# Relay.net
KiCad netlist of a schematic drawn in Altium Designer
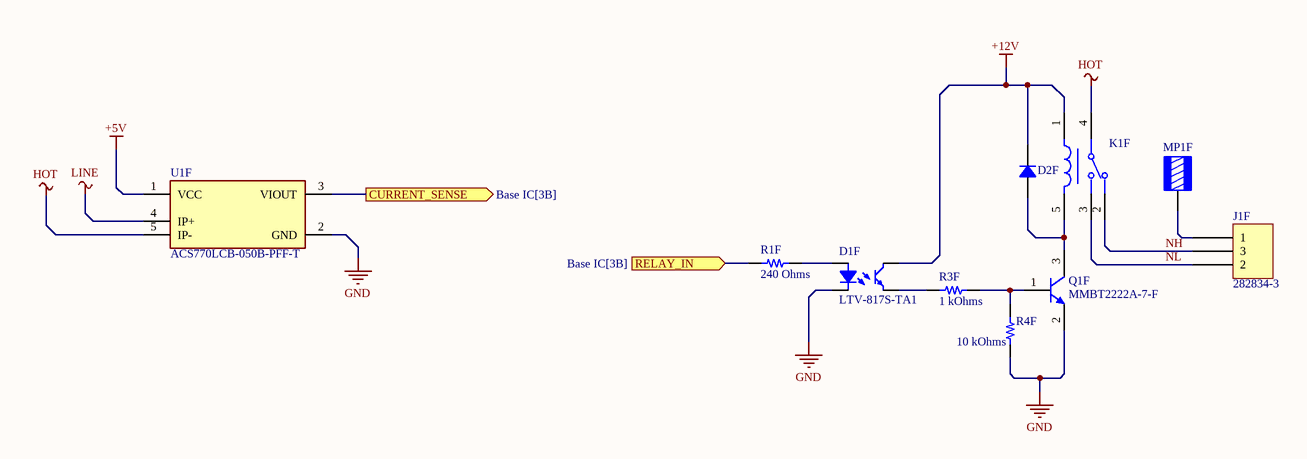
[diagram p0: Relay.SchDoc]

(export (version "E")
  (design (tool "Eeschema 10.0.6"))
  (components
    (comp (ref "D1F")
      (value "LTV-817S-TA1")
      (footprint "LITEON LTV-817")
      (description "OPTOISOLATR 5KV TRANSISTOR 4-SMD")
      (fields (field (name "MANUFACTURER") "Lite-On Inc."))
      (libsource (lib "Postgres Altium Library - altium_library") (part "Optoisolator"))
    )
    (comp (ref "D2F")
      (value "S2A-13-F")
      (footprint "DO214AA SMB")
      (description "DIODE GEN PURP 50V 1.5A SMB")
      (fields (field (name "MANUFACTURER") "Diodes Incorporated"))
      (libsource (lib "Postgres Altium Library - altium_library") (part "Diode"))
    )
    (comp (ref "J1F")
      (value "282834-3")
      (footprint "TE 282834-3")
      (description "TERM BLK 3P SIDE ENT 2.54MM PCB")
      (fields (field (name "VOLTAGE") "150V") (field (name "MANUFACTURER") "TE Connectivity AMP Connectors"))
      (libsource (lib "Postgres Altium Library - altium_library") (part "3 Pin"))
    )
    (comp (ref "K1F")
      (value "G2R-1-DC12")
      (footprint "FP-G2R-1-DC12-MFG")
      (description "RELAY GEN PURPOSE SPDT 10A 12V")
      (libsource (lib "Altium Content Vault") (part "ca5ce4f776bd4b8c9fc220deb446b63"))
    )
    (comp (ref "MP1F")
      (value "74650173R")
      (footprint "WURTH 74650173")
      (description "TERM REDCUBE M3 4PIN PCB")
      (fields (field (name "MANUFACTURER") "Würth Elektronik"))
      (libsource (lib "Postgres Altium Library - altium_library") (part "MOUNTING POINT"))
    )
    (comp (ref "Q1F")
      (value "MMBT2222A-7-F")
      (footprint "DIODES SOT-23-3")
      (description "TRANS NPN 40V 0.6A SOT23-3")
      (fields (field (name "MANUFACTURER") "Diodes Incorporated"))
      (libsource (lib "Postgres Altium Library - altium_library") (part "DIODES INC NPN SOT-23-3"))
    )
    (comp (ref "R1F")
      (value "240 Ohms")
      (footprint "RES 0603_1608")
      (description "RES 240 OHM 5% 1/8W 0603")
      (fields (field (name "PART NUMBER") "RK73B1JTTD241J") (field (name "TOLERANCE") "±5%"))
      (libsource (lib "Postgres Altium Library - altium_library") (part "Resistor"))
    )
    (comp (ref "R3F")
      (value "1 kOhms")
      (footprint "RES 0603_1608")
      (description "RES SMD 1K OHM 0.5% 1/10W 0603")
      (fields (field (name "PART NUMBER") "AT0603DRD071KL") (field (name "TOLERANCE") "±0.5%"))
      (libsource (lib "Postgres Altium Library - altium_library") (part "Resistor"))
    )
    (comp (ref "R4F")
      (value "10 kOhms")
      (footprint "RES 0603_1608")
      (description "RES SMD 10K OHM 0.1% 1/16W 0603")
      (fields (field (name "PART NUMBER") "CPF0603B10KE") (field (name "TOLERANCE") "±0.1%"))
      (libsource (lib "Postgres Altium Library - altium_library") (part "Resistor"))
    )
    (comp (ref "U1F")
      (value "ACS770LCB-050B-PFF-T")
      (footprint "FP-CB-5-PFF-MFG")
      (description "SENSOR CURRENT HALL 50A AC/DC")
      (libsource (lib "Altium Content Vault") (part "14cf2d2c5e445e47a38643444011565"))
    )
  )
  (nets
    (net (code "1") (name "+5V") (class "Default")
      (node (ref "U1F") (pin "1") (pinfunction "VCC_1") (pintype "power_in"))
    )
    (net (code "2") (name "+12V") (class "Default")
      (node (ref "D1F") (pin "4") (pinfunction "4_4") (pintype "passive"))
      (node (ref "D2F") (pin "2") (pinfunction "2_2") (pintype "passive"))
      (node (ref "K1F") (pin "1") (pinfunction "1_1") (pintype "passive"))
    )
    (net (code "3") (name "/CURRENT_SENSE") (class "Default")
      (node (ref "U1F") (pin "3") (pinfunction "VIOUT_3") (pintype "passive"))
    )
    (net (code "4") (name "/NH") (class "Default")
      (node (ref "J1F") (pin "3") (pinfunction "3_3") (pintype "passive"))
      (node (ref "K1F") (pin "2") (pinfunction "2_2") (pintype "passive"))
    )
    (net (code "5") (name "/NL") (class "Default")
      (node (ref "J1F") (pin "2") (pinfunction "2_2") (pintype "passive"))
      (node (ref "K1F") (pin "3") (pinfunction "3_3") (pintype "passive"))
    )
    (net (code "6") (name "/RELAY_IN") (class "Default")
      (node (ref "R1F") (pin "1") (pinfunction "1_1") (pintype "passive"))
    )
    (net (code "7") (name "GND") (class "Default")
      (node (ref "D1F") (pin "2") (pinfunction "2_2") (pintype "passive"))
      (node (ref "Q1F") (pin "2") (pinfunction "E_2") (pintype "passive"))
      (node (ref "R4F") (pin "1") (pinfunction "1_1") (pintype "passive"))
      (node (ref "U1F") (pin "2") (pinfunction "GND_2") (pintype "power_in"))
    )
    (net (code "8") (name "HOT") (class "Default")
      (node (ref "K1F") (pin "4") (pinfunction "4_4") (pintype "passive"))
      (node (ref "U1F") (pin "5") (pinfunction "IP-_5") (pintype "passive"))
    )
    (net (code "9") (name "LINE") (class "Default")
      (node (ref "U1F") (pin "4") (pinfunction "IP+_4") (pintype "passive"))
    )
    (net (code "10") (name "Net-(D1F-Pad1)") (class "Default")
      (node (ref "D1F") (pin "1") (pinfunction "1_1") (pintype "passive"))
      (node (ref "R1F") (pin "2") (pinfunction "2_2") (pintype "passive"))
    )
    (net (code "11") (name "Net-(D1F-Pad3)") (class "Default")
      (node (ref "D1F") (pin "3") (pinfunction "3_3") (pintype "passive"))
      (node (ref "R3F") (pin "1") (pinfunction "1_1") (pintype "passive"))
    )
    (net (code "12") (name "Net-(J1F-Pad1)") (class "Default")
      (node (ref "J1F") (pin "1") (pinfunction "1_1") (pintype "passive"))
      (node (ref "MP1F") (pin "1") (pinfunction "1_1") (pintype "passive"))
    )
    (net (code "13") (name "Net-(Q1F-B)") (class "Default")
      (node (ref "Q1F") (pin "1") (pinfunction "B_1") (pintype "passive"))
      (node (ref "R3F") (pin "2") (pinfunction "2_2") (pintype "passive"))
      (node (ref "R4F") (pin "2") (pinfunction "2_2") (pintype "passive"))
    )
    (net (code "14") (name "Net-(Q1F-C)") (class "Default")
      (node (ref "D2F") (pin "1") (pinfunction "1_1") (pintype "passive"))
      (node (ref "K1F") (pin "5") (pinfunction "5_5") (pintype "passive"))
      (node (ref "Q1F") (pin "3") (pinfunction "C_3") (pintype "passive"))
    )
  )
)
